# USB_Sentinel.net
KiCad netlist of a schematic drawn in EAGLE
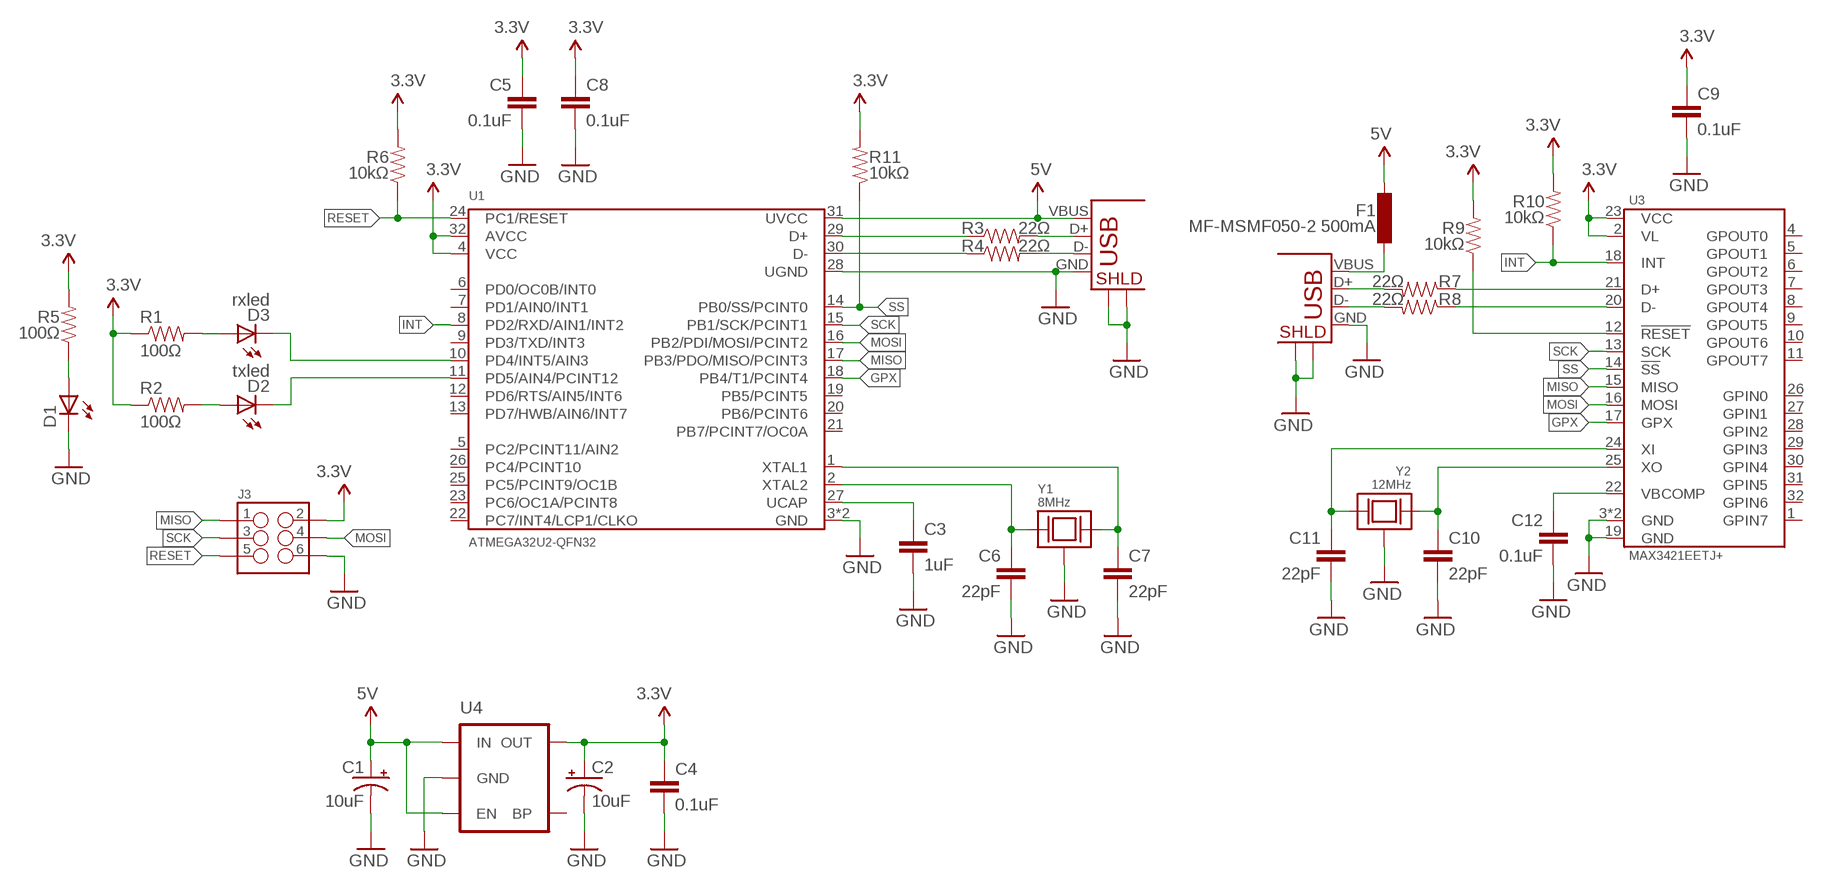
[diagram p0: schematic, sheet 1]

(export (version "E")
  (design (tool "Eeschema 10.0.6"))
  (components
    (comp (ref "C1")
      (value "10uF")
      (footprint "eagle-import:0805-CAP_POL")
      (libsource (lib "eagle-import") (part "CAP_POL0805"))
    )
    (comp (ref "C2")
      (value "10uF")
      (footprint "eagle-import:0805-CAP_POL")
      (libsource (lib "eagle-import") (part "CAP_POL0805"))
    )
    (comp (ref "C3")
      (value "1uF")
      (footprint "eagle-import:0402-CAP")
      (libsource (lib "eagle-import") (part "CAP0402-CAP"))
    )
    (comp (ref "C4")
      (value "0.1uF")
      (footprint "eagle-import:0402-CAP")
      (libsource (lib "eagle-import") (part "CAP0402-CAP"))
    )
    (comp (ref "C5")
      (value "0.1uF")
      (footprint "eagle-import:0402-CAP")
      (libsource (lib "eagle-import") (part "CAP0402-CAP"))
    )
    (comp (ref "C6")
      (value "22pF")
      (footprint "eagle-import:0402-CAP")
      (libsource (lib "eagle-import") (part "CAP0402-CAP"))
    )
    (comp (ref "C7")
      (value "22pF")
      (footprint "eagle-import:0402-CAP")
      (libsource (lib "eagle-import") (part "CAP0402-CAP"))
    )
    (comp (ref "C8")
      (value "0.1uF")
      (footprint "eagle-import:0402-CAP")
      (libsource (lib "eagle-import") (part "CAP0402-CAP"))
    )
    (comp (ref "C9")
      (value "0.1uF")
      (footprint "eagle-import:0402-CAP")
      (libsource (lib "eagle-import") (part "CAP0402-CAP"))
    )
    (comp (ref "C10")
      (value "22pF")
      (footprint "eagle-import:0402-CAP")
      (libsource (lib "eagle-import") (part "CAP0402-CAP"))
    )
    (comp (ref "C11")
      (value "22pF")
      (footprint "eagle-import:0402-CAP")
      (libsource (lib "eagle-import") (part "CAP0402-CAP"))
    )
    (comp (ref "C12")
      (value "0.1uF")
      (footprint "eagle-import:0402-CAP")
      (libsource (lib "eagle-import") (part "CAP0402-CAP"))
    )
    (comp (ref "D1")
      (value "LED0603")
      (footprint "eagle-import:LED-0603")
      (libsource (lib "eagle-import") (part "LED0603"))
    )
    (comp (ref "D2")
      (value "txled")
      (footprint "eagle-import:LED-0603")
      (libsource (lib "eagle-import") (part "LED0603"))
    )
    (comp (ref "D3")
      (value "rxled")
      (footprint "eagle-import:LED-0603")
      (libsource (lib "eagle-import") (part "LED0603"))
    )
    (comp (ref "F1")
      (value "MF-MSMF050-2 500mA")
      (footprint "eagle-import:L1812")
      (libsource (lib "eagle-import") (part "L-EUL1812"))
    )
    (comp (ref "J1")
      (value "USB+SHIELD-MICROB")
      (footprint "eagle-import:USB-MICROB")
      (libsource (lib "eagle-import") (part "USB+SHIELD-MICROB"))
    )
    (comp (ref "J2")
      (value "USB+SHIELD-A-S")
      (footprint "eagle-import:USB-A-S")
      (libsource (lib "eagle-import") (part "USB+SHIELD-A-S"))
    )
    (comp (ref "J3")
      (value "M03X2-50MIL")
      (footprint "eagle-import:M03X2-50MIL")
      (libsource (lib "eagle-import") (part "M03X2-50MIL"))
    )
    (comp (ref "R1")
      (value "100Ω")
      (footprint "eagle-import:0402-RES")
      (libsource (lib "eagle-import") (part "RESISTOR0402-RES"))
    )
    (comp (ref "R2")
      (value "100Ω")
      (footprint "eagle-import:0402-RES")
      (libsource (lib "eagle-import") (part "RESISTOR0402-RES"))
    )
    (comp (ref "R3")
      (value "22Ω")
      (footprint "eagle-import:0402-RES")
      (libsource (lib "eagle-import") (part "RESISTOR0402-RES"))
    )
    (comp (ref "R4")
      (value "22Ω")
      (footprint "eagle-import:0402-RES")
      (libsource (lib "eagle-import") (part "RESISTOR0402-RES"))
    )
    (comp (ref "R5")
      (value "100Ω")
      (footprint "eagle-import:0402-RES")
      (libsource (lib "eagle-import") (part "RESISTOR0402-RES"))
    )
    (comp (ref "R6")
      (value "10kΩ")
      (footprint "eagle-import:0402-RES")
      (libsource (lib "eagle-import") (part "RESISTOR0402-RES"))
    )
    (comp (ref "R7")
      (value "22Ω")
      (footprint "eagle-import:0402-RES")
      (libsource (lib "eagle-import") (part "RESISTOR0402-RES"))
    )
    (comp (ref "R8")
      (value "22Ω")
      (footprint "eagle-import:0402-RES")
      (libsource (lib "eagle-import") (part "RESISTOR0402-RES"))
    )
    (comp (ref "R9")
      (value "10kΩ")
      (footprint "eagle-import:0402-RES")
      (libsource (lib "eagle-import") (part "RESISTOR0402-RES"))
    )
    (comp (ref "R10")
      (value "10kΩ")
      (footprint "eagle-import:0402-RES")
      (libsource (lib "eagle-import") (part "RESISTOR0402-RES"))
    )
    (comp (ref "R11")
      (value "10kΩ")
      (footprint "eagle-import:0402-RES")
      (libsource (lib "eagle-import") (part "RESISTOR0402-RES"))
    )
    (comp (ref "U1")
      (value "ATMEGA32U2-QFN32")
      (footprint "eagle-import:QFN-32")
      (libsource (lib "eagle-import") (part "ATMEGA32U2-QFN32"))
    )
    (comp (ref "U3")
      (value "MAX3421EETJ+")
      (footprint "eagle-import:QFN-32")
      (libsource (lib "eagle-import") (part "MAX3421EETJ+"))
    )
    (comp (ref "U4")
      (value "V_REG_LDOSMD")
      (footprint "eagle-import:SOT23-5")
      (libsource (lib "eagle-import") (part "V_REG_LDOSMD"))
    )
    (comp (ref "Y1")
      (value "8MHz")
      (footprint "eagle-import:CRYSTAL-5X3.2")
      (libsource (lib "eagle-import") (part "CRYSTAL-5X3.2"))
    )
    (comp (ref "Y2")
      (value "12MHz")
      (footprint "eagle-import:ECX-32")
      (libsource (lib "eagle-import") (part "CRYSTAL-ECX32"))
    )
  )
  (nets
    (net (code "1") (name "3.3V") (class "Default")
      (node (ref "C2") (pin "A") (pinfunction "+_A") (pintype "passive"))
      (node (ref "C4") (pin "1") (pinfunction "1_1") (pintype "passive"))
      (node (ref "C5") (pin "1") (pinfunction "1_1") (pintype "passive"))
      (node (ref "C8") (pin "1") (pinfunction "1_1") (pintype "passive"))
      (node (ref "C9") (pin "1") (pinfunction "1_1") (pintype "passive"))
      (node (ref "J3") (pin "2") (pinfunction "2_2") (pintype "bidirectional"))
      (node (ref "R1") (pin "1") (pinfunction "1_1") (pintype "passive"))
      (node (ref "R10") (pin "2") (pinfunction "2_2") (pintype "passive"))
      (node (ref "R11") (pin "2") (pinfunction "2_2") (pintype "passive"))
      (node (ref "R2") (pin "1") (pinfunction "1_1") (pintype "passive"))
      (node (ref "R5") (pin "2") (pinfunction "2_2") (pintype "passive"))
      (node (ref "R6") (pin "2") (pinfunction "2_2") (pintype "passive"))
      (node (ref "R9") (pin "2") (pinfunction "2_2") (pintype "passive"))
      (node (ref "U1") (pin "32") (pinfunction "AVCC_32") (pintype "bidirectional"))
      (node (ref "U1") (pin "4") (pinfunction "VCC_4") (pintype "bidirectional"))
      (node (ref "U3") (pin "2") (pinfunction "VL_2") (pintype "bidirectional"))
      (node (ref "U3") (pin "23") (pinfunction "VCC_23") (pintype "bidirectional"))
      (node (ref "U4") (pin "5") (pinfunction "OUT_5") (pintype "passive"))
    )
    (net (code "2") (name "5V") (class "Default")
      (node (ref "C1") (pin "A") (pinfunction "+_A") (pintype "passive"))
      (node (ref "F1") (pin "1") (pinfunction "1_1") (pintype "passive"))
      (node (ref "J1") (pin "VBUS") (pinfunction "VBUS_VBUS") (pintype "bidirectional"))
      (node (ref "U1") (pin "31") (pinfunction "UVCC_31") (pintype "bidirectional"))
      (node (ref "U4") (pin "1") (pinfunction "IN_1") (pintype "input"))
      (node (ref "U4") (pin "3") (pinfunction "EN_3") (pintype "input"))
    )
    (net (code "3") (name "GND") (class "Default")
      (node (ref "C1") (pin "C") (pinfunction "-_C") (pintype "passive"))
      (node (ref "C10") (pin "2") (pinfunction "2_2") (pintype "passive"))
      (node (ref "C11") (pin "2") (pinfunction "2_2") (pintype "passive"))
      (node (ref "C12") (pin "2") (pinfunction "2_2") (pintype "passive"))
      (node (ref "C2") (pin "C") (pinfunction "-_C") (pintype "passive"))
      (node (ref "C3") (pin "2") (pinfunction "2_2") (pintype "passive"))
      (node (ref "C4") (pin "2") (pinfunction "2_2") (pintype "passive"))
      (node (ref "C5") (pin "2") (pinfunction "2_2") (pintype "passive"))
      (node (ref "C6") (pin "2") (pinfunction "2_2") (pintype "passive"))
      (node (ref "C7") (pin "2") (pinfunction "2_2") (pintype "passive"))
      (node (ref "C8") (pin "2") (pinfunction "2_2") (pintype "passive"))
      (node (ref "C9") (pin "2") (pinfunction "2_2") (pintype "passive"))
      (node (ref "D1") (pin "C") (pinfunction "C_C") (pintype "passive"))
      (node (ref "J1") (pin "GND") (pinfunction "GND_GND") (pintype "bidirectional"))
      (node (ref "J1") (pin "MT1") (pinfunction "P$1_MT1") (pintype "bidirectional"))
      (node (ref "J1") (pin "MT2") (pinfunction "P$2_MT2") (pintype "bidirectional"))
      (node (ref "J1") (pin "P$1") (pinfunction "P$1_P$1") (pintype "bidirectional"))
      (node (ref "J1") (pin "P$2") (pinfunction "P$2_P$2") (pintype "bidirectional"))
      (node (ref "J2") (pin "GND") (pinfunction "GND_GND") (pintype "bidirectional"))
      (node (ref "J2") (pin "P$5") (pinfunction "P$1_P$5") (pintype "bidirectional"))
      (node (ref "J2") (pin "P$6") (pinfunction "P$2_P$6") (pintype "bidirectional"))
      (node (ref "J3") (pin "6") (pinfunction "6_6") (pintype "bidirectional"))
      (node (ref "U1") (pin "28") (pinfunction "UGND_28") (pintype "bidirectional"))
      (node (ref "U1") (pin "3") (pinfunction "GND_3") (pintype "bidirectional"))
      (node (ref "U1") (pin "EP") (pinfunction "GND_EP") (pintype "bidirectional"))
      (node (ref "U3") (pin "19") (pinfunction "GND_19") (pintype "bidirectional"))
      (node (ref "U3") (pin "3") (pinfunction "GND_3") (pintype "bidirectional"))
      (node (ref "U3") (pin "EP") (pinfunction "GND_EP") (pintype "bidirectional"))
      (node (ref "U4") (pin "2") (pinfunction "GND_2") (pintype "input"))
      (node (ref "Y1") (pin "2") (pinfunction "GND_2") (pintype "bidirectional"))
      (node (ref "Y1") (pin "4") (pinfunction "GND_4") (pintype "bidirectional"))
      (node (ref "Y2") (pin "2") (pinfunction "GND_2") (pintype "bidirectional"))
      (node (ref "Y2") (pin "4") (pinfunction "GND_4") (pintype "bidirectional"))
    )
    (net (code "4") (name "GPX") (class "Default")
      (node (ref "U1") (pin "18") (pinfunction "PB4/T1/PCINT4_18") (pintype "bidirectional"))
      (node (ref "U3") (pin "17") (pinfunction "GPX_17") (pintype "bidirectional"))
    )
    (net (code "5") (name "INT") (class "Default")
      (node (ref "R10") (pin "1") (pinfunction "1_1") (pintype "passive"))
      (node (ref "U1") (pin "8") (pinfunction "PD2/RXD/AIN1/INT2_8") (pintype "bidirectional"))
      (node (ref "U3") (pin "18") (pinfunction "INT_18") (pintype "bidirectional"))
    )
    (net (code "6") (name "MISO") (class "Default")
      (node (ref "J3") (pin "1") (pinfunction "1_1") (pintype "bidirectional"))
      (node (ref "U1") (pin "17") (pinfunction "PB3/PDO/MISO/PCINT3_17") (pintype "bidirectional"))
      (node (ref "U3") (pin "15") (pinfunction "MISO_15") (pintype "bidirectional"))
    )
    (net (code "7") (name "MOSI") (class "Default")
      (node (ref "J3") (pin "4") (pinfunction "4_4") (pintype "bidirectional"))
      (node (ref "U1") (pin "16") (pinfunction "PB2/PDI/MOSI/PCINT2_16") (pintype "bidirectional"))
      (node (ref "U3") (pin "16") (pinfunction "MOSI_16") (pintype "bidirectional"))
    )
    (net (code "8") (name "Net-(D1-PadA)") (class "Default")
      (node (ref "D1") (pin "A") (pinfunction "A_A") (pintype "passive"))
      (node (ref "R5") (pin "1") (pinfunction "1_1") (pintype "passive"))
    )
    (net (code "9") (name "Net-(D2-PadA)") (class "Default")
      (node (ref "D2") (pin "A") (pinfunction "A_A") (pintype "passive"))
      (node (ref "R2") (pin "2") (pinfunction "2_2") (pintype "passive"))
    )
    (net (code "10") (name "Net-(D3-PadA)") (class "Default")
      (node (ref "D3") (pin "A") (pinfunction "A_A") (pintype "passive"))
      (node (ref "R1") (pin "2") (pinfunction "2_2") (pintype "passive"))
    )
    (net (code "11") (name "Net-(F1-Pad2)") (class "Default")
      (node (ref "F1") (pin "2") (pinfunction "2_2") (pintype "passive"))
      (node (ref "J2") (pin "VBUS") (pinfunction "VBUS_VBUS") (pintype "bidirectional"))
    )
    (net (code "12") (name "Net-(J1-PadD+)") (class "Default")
      (node (ref "J1") (pin "D+") (pinfunction "D+_D+") (pintype "bidirectional"))
      (node (ref "R3") (pin "2") (pinfunction "2_2") (pintype "passive"))
    )
    (net (code "13") (name "Net-(J1-PadD-)") (class "Default")
      (node (ref "J1") (pin "D-") (pinfunction "D-_D-") (pintype "bidirectional"))
      (node (ref "R4") (pin "2") (pinfunction "2_2") (pintype "passive"))
    )
    (net (code "14") (name "Net-(J2-PadD+)") (class "Default")
      (node (ref "J2") (pin "D+") (pinfunction "D+_D+") (pintype "bidirectional"))
      (node (ref "R7") (pin "2") (pinfunction "2_2") (pintype "passive"))
    )
    (net (code "15") (name "Net-(J2-PadD-)") (class "Default")
      (node (ref "J2") (pin "D-") (pinfunction "D-_D-") (pintype "bidirectional"))
      (node (ref "R8") (pin "2") (pinfunction "2_2") (pintype "passive"))
    )
    (net (code "16") (name "Net-(U1-D+)") (class "Default")
      (node (ref "R3") (pin "1") (pinfunction "1_1") (pintype "passive"))
      (node (ref "U1") (pin "29") (pinfunction "D+_29") (pintype "bidirectional"))
    )
    (net (code "17") (name "Net-(U1-D-)") (class "Default")
      (node (ref "R4") (pin "1") (pinfunction "1_1") (pintype "passive"))
      (node (ref "U1") (pin "30") (pinfunction "D-_30") (pintype "bidirectional"))
    )
    (net (code "18") (name "Net-(U1-PD4{slash}INT5{slash}AIN3)") (class "Default")
      (node (ref "D3") (pin "C") (pinfunction "C_C") (pintype "passive"))
      (node (ref "U1") (pin "10") (pinfunction "PD4/INT5/AIN3_10") (pintype "bidirectional"))
    )
    (net (code "19") (name "Net-(U1-PD5{slash}AIN4{slash}PCINT12)") (class "Default")
      (node (ref "D2") (pin "C") (pinfunction "C_C") (pintype "passive"))
      (node (ref "U1") (pin "11") (pinfunction "PD5/AIN4/PCINT12_11") (pintype "bidirectional"))
    )
    (net (code "20") (name "Net-(U1-UCAP)") (class "Default")
      (node (ref "C3") (pin "1") (pinfunction "1_1") (pintype "passive"))
      (node (ref "U1") (pin "27") (pinfunction "UCAP_27") (pintype "bidirectional"))
    )
    (net (code "21") (name "Net-(U1-XTAL1)") (class "Default")
      (node (ref "C7") (pin "1") (pinfunction "1_1") (pintype "passive"))
      (node (ref "U1") (pin "1") (pinfunction "XTAL1_1") (pintype "bidirectional"))
      (node (ref "Y1") (pin "3") (pinfunction "3_3") (pintype "passive"))
    )
    (net (code "22") (name "Net-(U1-XTAL2)") (class "Default")
      (node (ref "C6") (pin "1") (pinfunction "1_1") (pintype "passive"))
      (node (ref "U1") (pin "2") (pinfunction "XTAL2_2") (pintype "bidirectional"))
      (node (ref "Y1") (pin "1") (pinfunction "1_1") (pintype "passive"))
    )
    (net (code "23") (name "Net-(U3-D+)") (class "Default")
      (node (ref "R7") (pin "1") (pinfunction "1_1") (pintype "passive"))
      (node (ref "U3") (pin "21") (pinfunction "D+_21") (pintype "bidirectional"))
    )
    (net (code "24") (name "Net-(U3-D-)") (class "Default")
      (node (ref "R8") (pin "1") (pinfunction "1_1") (pintype "passive"))
      (node (ref "U3") (pin "20") (pinfunction "D-_20") (pintype "bidirectional"))
    )
    (net (code "25") (name "Net-(U3-VBCOMP)") (class "Default")
      (node (ref "C12") (pin "1") (pinfunction "1_1") (pintype "passive"))
      (node (ref "U3") (pin "22") (pinfunction "VBCOMP_22") (pintype "bidirectional"))
    )
    (net (code "26") (name "Net-(U3-XI)") (class "Default")
      (node (ref "C11") (pin "1") (pinfunction "1_1") (pintype "passive"))
      (node (ref "U3") (pin "24") (pinfunction "XI_24") (pintype "bidirectional"))
      (node (ref "Y2") (pin "3") (pinfunction "3_3") (pintype "passive"))
    )
    (net (code "27") (name "Net-(U3-XO)") (class "Default")
      (node (ref "C10") (pin "1") (pinfunction "1_1") (pintype "passive"))
      (node (ref "U3") (pin "25") (pinfunction "XO_25") (pintype "bidirectional"))
      (node (ref "Y2") (pin "1") (pinfunction "1_1") (pintype "passive"))
    )
    (net (code "28") (name "Net-(U3-~{RESET})") (class "Default")
      (node (ref "R9") (pin "1") (pinfunction "1_1") (pintype "passive"))
      (node (ref "U3") (pin "12") (pinfunction "~{RESET}_12") (pintype "bidirectional"))
    )
    (net (code "29") (name "RESET") (class "Default")
      (node (ref "J3") (pin "5") (pinfunction "5_5") (pintype "bidirectional"))
      (node (ref "R6") (pin "1") (pinfunction "1_1") (pintype "passive"))
      (node (ref "U1") (pin "24") (pinfunction "PC1/RESET_24") (pintype "bidirectional"))
    )
    (net (code "30") (name "SCK") (class "Default")
      (node (ref "J3") (pin "3") (pinfunction "3_3") (pintype "bidirectional"))
      (node (ref "U1") (pin "15") (pinfunction "PB1/SCK/PCINT1_15") (pintype "bidirectional"))
      (node (ref "U3") (pin "13") (pinfunction "SCK_13") (pintype "bidirectional"))
    )
    (net (code "31") (name "SS") (class "Default")
      (node (ref "R11") (pin "1") (pinfunction "1_1") (pintype "passive"))
      (node (ref "U1") (pin "14") (pinfunction "PB0/SS/PCINT0_14") (pintype "bidirectional"))
      (node (ref "U3") (pin "14") (pinfunction "~{SS}_14") (pintype "bidirectional"))
    )
    (net (code "32") (name "unconnected-(U1-PB5{slash}PCINT5-Pad19)") (class "Default")
      (node (ref "U1") (pin "19") (pinfunction "PB5/PCINT5_19") (pintype "bidirectional"))
    )
    (net (code "33") (name "unconnected-(U1-PB6{slash}PCINT6-Pad20)") (class "Default")
      (node (ref "U1") (pin "20") (pinfunction "PB6/PCINT6_20") (pintype "bidirectional"))
    )
    (net (code "34") (name "unconnected-(U1-PB7{slash}PCINT7{slash}OC0A-Pad21)") (class "Default")
      (node (ref "U1") (pin "21") (pinfunction "PB7/PCINT7/OC0A_21") (pintype "bidirectional"))
    )
    (net (code "35") (name "unconnected-(U1-PC2{slash}PCINT11{slash}AIN2-Pad5)") (class "Default")
      (node (ref "U1") (pin "5") (pinfunction "PC2/PCINT11/AIN2_5") (pintype "bidirectional"))
    )
    (net (code "36") (name "unconnected-(U1-PC4{slash}PCINT10-Pad26)") (class "Default")
      (node (ref "U1") (pin "26") (pinfunction "PC4/PCINT10_26") (pintype "bidirectional"))
    )
    (net (code "37") (name "unconnected-(U1-PC5{slash}PCINT9{slash}OC1B-Pad25)") (class "Default")
      (node (ref "U1") (pin "25") (pinfunction "PC5/PCINT9/OC1B_25") (pintype "bidirectional"))
    )
    (net (code "38") (name "unconnected-(U1-PC6{slash}OC1A{slash}PCINT8-Pad23)") (class "Default")
      (node (ref "U1") (pin "23") (pinfunction "PC6/OC1A/PCINT8_23") (pintype "bidirectional"))
    )
    (net (code "39") (name "unconnected-(U1-PC7{slash}INT4{slash}LCP1{slash}CLKO-Pad22)") (class "Default")
      (node (ref "U1") (pin "22") (pinfunction "PC7/INT4/LCP1/CLKO_22") (pintype "bidirectional"))
    )
    (net (code "40") (name "unconnected-(U1-PD0{slash}OC0B{slash}INT0-Pad6)") (class "Default")
      (node (ref "U1") (pin "6") (pinfunction "PD0/OC0B/INT0_6") (pintype "bidirectional"))
    )
    (net (code "41") (name "unconnected-(U1-PD1{slash}AIN0{slash}INT1-Pad7)") (class "Default")
      (node (ref "U1") (pin "7") (pinfunction "PD1/AIN0/INT1_7") (pintype "bidirectional"))
    )
    (net (code "42") (name "unconnected-(U1-PD3{slash}TXD{slash}INT3-Pad9)") (class "Default")
      (node (ref "U1") (pin "9") (pinfunction "PD3/TXD/INT3_9") (pintype "bidirectional"))
    )
    (net (code "43") (name "unconnected-(U1-PD6{slash}RTS{slash}AIN5{slash}INT6-Pad12)") (class "Default")
      (node (ref "U1") (pin "12") (pinfunction "PD6/RTS/AIN5/INT6_12") (pintype "bidirectional"))
    )
    (net (code "44") (name "unconnected-(U1-PD7{slash}HWB{slash}AIN6{slash}INT7-Pad13)") (class "Default")
      (node (ref "U1") (pin "13") (pinfunction "PD7/HWB/AIN6/INT7_13") (pintype "bidirectional"))
    )
    (net (code "45") (name "unconnected-(U3-GPIN0-Pad26)") (class "Default")
      (node (ref "U3") (pin "26") (pinfunction "GPIN0_26") (pintype "bidirectional"))
    )
    (net (code "46") (name "unconnected-(U3-GPIN1-Pad27)") (class "Default")
      (node (ref "U3") (pin "27") (pinfunction "GPIN1_27") (pintype "bidirectional"))
    )
    (net (code "47") (name "unconnected-(U3-GPIN2-Pad28)") (class "Default")
      (node (ref "U3") (pin "28") (pinfunction "GPIN2_28") (pintype "bidirectional"))
    )
    (net (code "48") (name "unconnected-(U3-GPIN3-Pad29)") (class "Default")
      (node (ref "U3") (pin "29") (pinfunction "GPIN3_29") (pintype "bidirectional"))
    )
    (net (code "49") (name "unconnected-(U3-GPIN4-Pad30)") (class "Default")
      (node (ref "U3") (pin "30") (pinfunction "GPIN4_30") (pintype "bidirectional"))
    )
    (net (code "50") (name "unconnected-(U3-GPIN5-Pad31)") (class "Default")
      (node (ref "U3") (pin "31") (pinfunction "GPIN5_31") (pintype "bidirectional"))
    )
    (net (code "51") (name "unconnected-(U3-GPIN6-Pad32)") (class "Default")
      (node (ref "U3") (pin "32") (pinfunction "GPIN6_32") (pintype "bidirectional"))
    )
    (net (code "52") (name "unconnected-(U3-GPIN7-Pad1)") (class "Default")
      (node (ref "U3") (pin "1") (pinfunction "GPIN7_1") (pintype "bidirectional"))
    )
    (net (code "53") (name "unconnected-(U3-GPOUT0-Pad4)") (class "Default")
      (node (ref "U3") (pin "4") (pinfunction "GPOUT0_4") (pintype "bidirectional"))
    )
    (net (code "54") (name "unconnected-(U3-GPOUT1-Pad5)") (class "Default")
      (node (ref "U3") (pin "5") (pinfunction "GPOUT1_5") (pintype "bidirectional"))
    )
    (net (code "55") (name "unconnected-(U3-GPOUT2-Pad6)") (class "Default")
      (node (ref "U3") (pin "6") (pinfunction "GPOUT2_6") (pintype "bidirectional"))
    )
    (net (code "56") (name "unconnected-(U3-GPOUT3-Pad7)") (class "Default")
      (node (ref "U3") (pin "7") (pinfunction "GPOUT3_7") (pintype "bidirectional"))
    )
    (net (code "57") (name "unconnected-(U3-GPOUT4-Pad8)") (class "Default")
      (node (ref "U3") (pin "8") (pinfunction "GPOUT4_8") (pintype "bidirectional"))
    )
    (net (code "58") (name "unconnected-(U3-GPOUT5-Pad9)") (class "Default")
      (node (ref "U3") (pin "9") (pinfunction "GPOUT5_9") (pintype "bidirectional"))
    )
    (net (code "59") (name "unconnected-(U3-GPOUT6-Pad10)") (class "Default")
      (node (ref "U3") (pin "10") (pinfunction "GPOUT6_10") (pintype "bidirectional"))
    )
    (net (code "60") (name "unconnected-(U3-GPOUT7-Pad11)") (class "Default")
      (node (ref "U3") (pin "11") (pinfunction "GPOUT7_11") (pintype "bidirectional"))
    )
    (net (code "61") (name "unconnected-(U4-BP-Pad4)") (class "Default")
      (node (ref "U4") (pin "4") (pinfunction "BP_4") (pintype "input"))
    )
  )
)
